# Traffic_Light_Controller.net
KiCad netlist of a schematic drawn in EAGLE
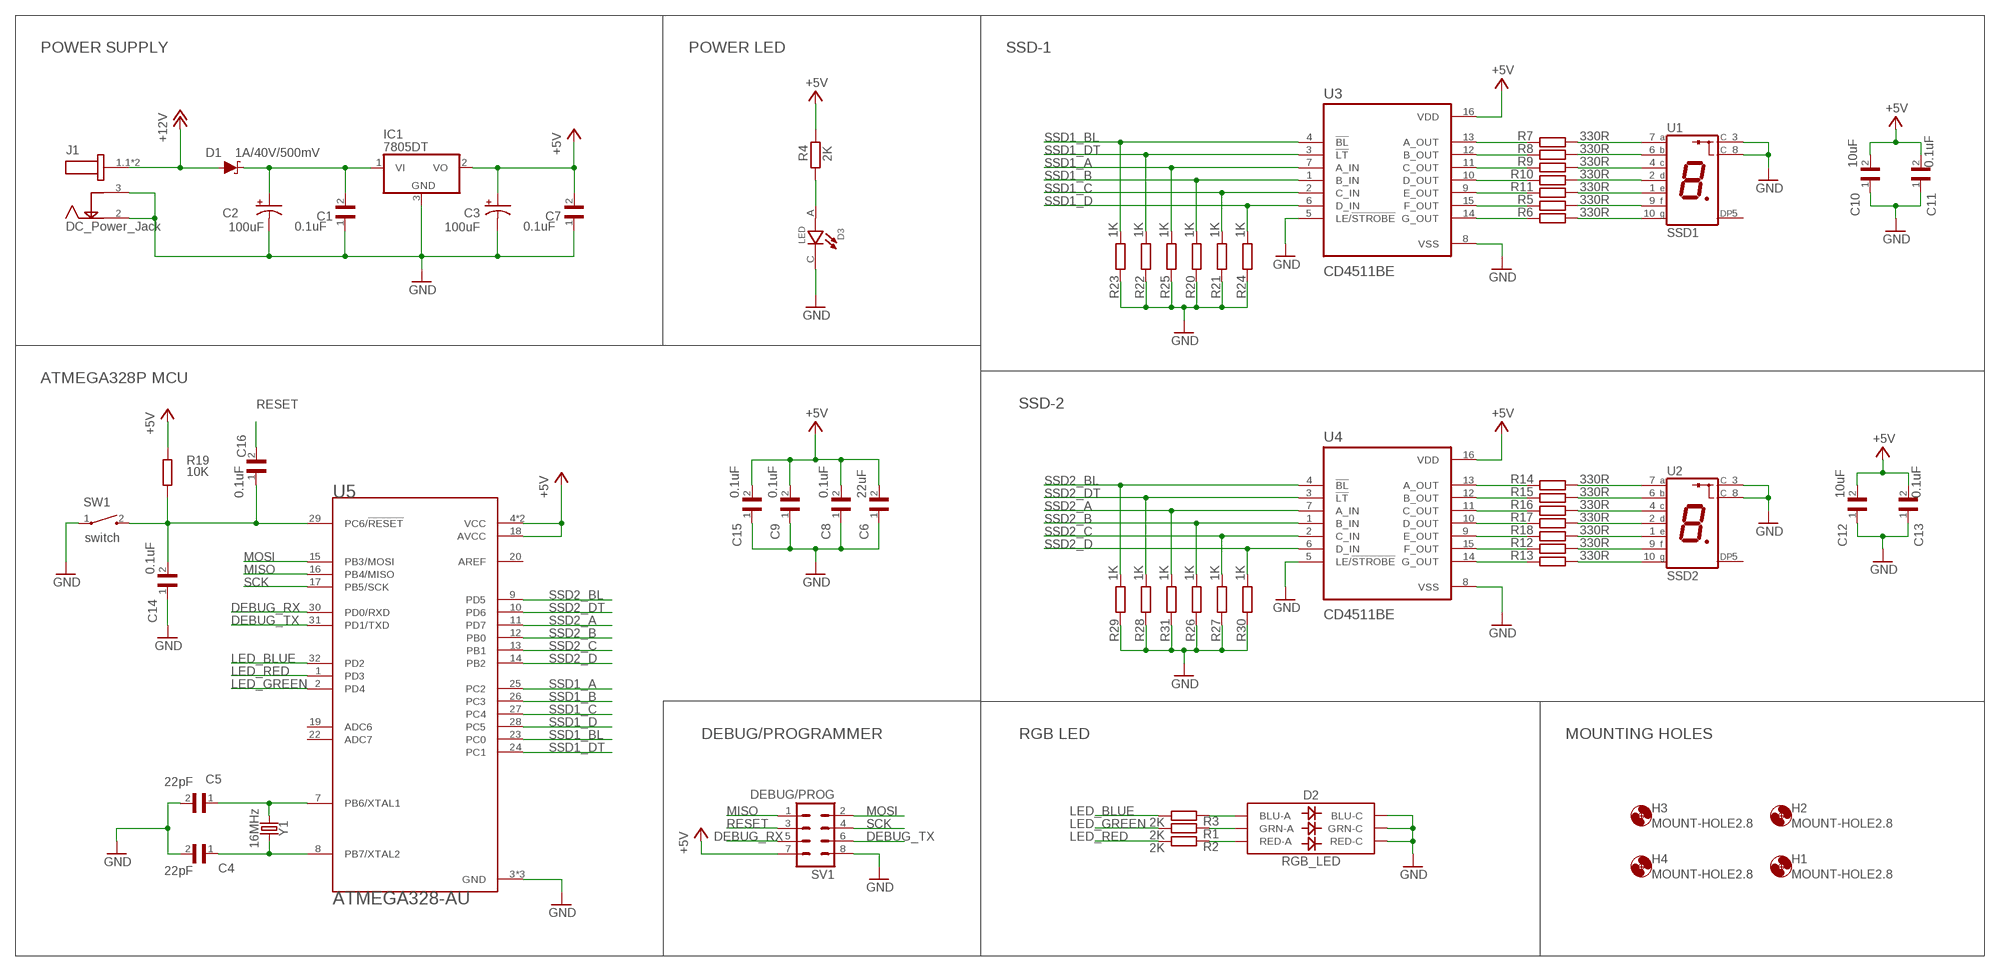
[diagram p0: schematic, sheet 1]

(export (version "E")
  (design (tool "Eeschema 10.0.6"))
  (components
    (comp (ref "C1")
      (value "0.1uF")
      (footprint "eagle-import:C0603")
      (fields (field (name "MF") "TDK") (field (name "MP") "CGA3E2X7R1H104K080AA"))
      (libsource (lib "eagle-import") (part "CAPACITOR"))
    )
    (comp (ref "C2")
      (value "100uF")
      (footprint "eagle-import:CPOL-RADIAL-2.5MM-6.5MM")
      (libsource (lib "eagle-import") (part "100UF-POLAR-RADIAL-2.5MM-25V-20%"))
    )
    (comp (ref "C3")
      (value "100uF")
      (footprint "eagle-import:CPOL-RADIAL-2.5MM-6.5MM")
      (libsource (lib "eagle-import") (part "100UF-POLAR-RADIAL-2.5MM-25V-20%"))
    )
    (comp (ref "C4")
      (value "22pF")
      (footprint "eagle-import:C0603")
      (fields (field (name "MF") "TDK") (field (name "MP") "CGA3E2X7R1H104K080AA"))
      (libsource (lib "eagle-import") (part "CAPACITOR"))
    )
    (comp (ref "C5")
      (value "22pF")
      (footprint "eagle-import:C0603")
      (fields (field (name "MF") "TDK") (field (name "MP") "CGA3E2X7R1H104K080AA"))
      (libsource (lib "eagle-import") (part "CAPACITOR"))
    )
    (comp (ref "C6")
      (value "22uF")
      (footprint "eagle-import:C0603")
      (fields (field (name "MF") "TDK") (field (name "MP") "CGA3E2X7R1H104K080AA"))
      (libsource (lib "eagle-import") (part "CAPACITOR"))
    )
    (comp (ref "C7")
      (value "0.1uF")
      (footprint "eagle-import:C0603")
      (fields (field (name "MF") "TDK") (field (name "MP") "CGA3E2X7R1H104K080AA"))
      (libsource (lib "eagle-import") (part "CAPACITOR"))
    )
    (comp (ref "C8")
      (value "0.1uF")
      (footprint "eagle-import:C0603")
      (fields (field (name "MF") "TDK") (field (name "MP") "CGA3E2X7R1H104K080AA"))
      (libsource (lib "eagle-import") (part "CAPACITOR"))
    )
    (comp (ref "C9")
      (value "0.1uF")
      (footprint "eagle-import:C0603")
      (fields (field (name "MF") "TDK") (field (name "MP") "CGA3E2X7R1H104K080AA"))
      (libsource (lib "eagle-import") (part "CAPACITOR"))
    )
    (comp (ref "C10")
      (value "10uF")
      (footprint "eagle-import:C0603")
      (fields (field (name "MF") "TDK") (field (name "MP") "CGA3E2X7R1H104K080AA"))
      (libsource (lib "eagle-import") (part "CAPACITOR"))
    )
    (comp (ref "C11")
      (value "0.1uF")
      (footprint "eagle-import:C0603")
      (fields (field (name "MF") "TDK") (field (name "MP") "CGA3E2X7R1H104K080AA"))
      (libsource (lib "eagle-import") (part "CAPACITOR"))
    )
    (comp (ref "C12")
      (value "10uF")
      (footprint "eagle-import:C0603")
      (fields (field (name "MF") "TDK") (field (name "MP") "CGA3E2X7R1H104K080AA"))
      (libsource (lib "eagle-import") (part "CAPACITOR"))
    )
    (comp (ref "C13")
      (value "0.1uF")
      (footprint "eagle-import:C0603")
      (fields (field (name "MF") "TDK") (field (name "MP") "CGA3E2X7R1H104K080AA"))
      (libsource (lib "eagle-import") (part "CAPACITOR"))
    )
    (comp (ref "C14")
      (value "0.1uF")
      (footprint "eagle-import:C0603")
      (fields (field (name "MF") "TDK") (field (name "MP") "CGA3E2X7R1H104K080AA"))
      (libsource (lib "eagle-import") (part "CAPACITOR"))
    )
    (comp (ref "C15")
      (value "0.1uF")
      (footprint "eagle-import:C0603")
      (fields (field (name "MF") "TDK") (field (name "MP") "CGA3E2X7R1H104K080AA"))
      (libsource (lib "eagle-import") (part "CAPACITOR"))
    )
    (comp (ref "C16")
      (value "0.1uF")
      (footprint "eagle-import:C0603")
      (fields (field (name "MF") "TDK") (field (name "MP") "CGA3E2X7R1H104K080AA"))
      (libsource (lib "eagle-import") (part "CAPACITOR"))
    )
    (comp (ref "D1")
      (value "1A/40V/500mV")
      (footprint "eagle-import:SMA-DIODE")
      (libsource (lib "eagle-import") (part "DIODE-SCHOTTKY-SS14"))
    )
    (comp (ref "D2")
      (value "RGB_LED")
      (footprint "eagle-import:LED-TRICOLOR-5050")
      (libsource (lib "eagle-import") (part "LED-RGBNO_IC"))
    )
    (comp (ref "D3")
      (value "LED")
      (footprint "eagle-import:LEDC1608X65N")
      (fields (field (name "MF") "Lite-On") (field (name "MP") "LTW-C191TLA"))
      (libsource (lib "eagle-import") (part "LTW-C191TLA"))
    )
    (comp (ref "H1")
      (value "MOUNT-HOLE2.8")
      (footprint "eagle-import:2,8")
      (libsource (lib "eagle-import") (part "MOUNT-HOLE2.8"))
    )
    (comp (ref "H2")
      (value "MOUNT-HOLE2.8")
      (footprint "eagle-import:2,8")
      (libsource (lib "eagle-import") (part "MOUNT-HOLE2.8"))
    )
    (comp (ref "H3")
      (value "MOUNT-HOLE2.8")
      (footprint "eagle-import:2,8")
      (libsource (lib "eagle-import") (part "MOUNT-HOLE2.8"))
    )
    (comp (ref "H4")
      (value "MOUNT-HOLE2.8")
      (footprint "eagle-import:2,8")
      (libsource (lib "eagle-import") (part "MOUNT-HOLE2.8"))
    )
    (comp (ref "IC1")
      (value "7805DT")
      (footprint "eagle-import:TO252")
      (libsource (lib "eagle-import") (part "78DT05"))
    )
    (comp (ref "J1")
      (value "DC_Power_Jack")
      (footprint "eagle-import:GCT_DCJ200-05-A-XX-X_REVA")
      (fields (field (name "MF") "Global Connector Technology") (field (name "MP") "DCJ200-05-A-K1-A"))
      (libsource (lib "eagle-import") (part "DCJ200-05-A-XX-X_REVA"))
    )
    (comp (ref "R1")
      (value "2K")
      (footprint "eagle-import:R0603")
      (fields (field (name "MF") "Yageo"))
      (libsource (lib "eagle-import") (part "RESISTOR"))
    )
    (comp (ref "R2")
      (value "2K")
      (footprint "eagle-import:R0603")
      (fields (field (name "MF") "Yageo"))
      (libsource (lib "eagle-import") (part "RESISTOR"))
    )
    (comp (ref "R3")
      (value "2K")
      (footprint "eagle-import:R0603")
      (fields (field (name "MF") "Yageo"))
      (libsource (lib "eagle-import") (part "RESISTOR"))
    )
    (comp (ref "R4")
      (value "2K")
      (footprint "eagle-import:R0603")
      (fields (field (name "MF") "Yageo"))
      (libsource (lib "eagle-import") (part "RESISTOR"))
    )
    (comp (ref "R5")
      (value "330R")
      (footprint "eagle-import:R0603")
      (fields (field (name "MF") "Yageo"))
      (libsource (lib "eagle-import") (part "RESISTOR"))
    )
    (comp (ref "R6")
      (value "330R")
      (footprint "eagle-import:R0603")
      (fields (field (name "MF") "Yageo"))
      (libsource (lib "eagle-import") (part "RESISTOR"))
    )
    (comp (ref "R7")
      (value "330R")
      (footprint "eagle-import:R0603")
      (fields (field (name "MF") "Yageo"))
      (libsource (lib "eagle-import") (part "RESISTOR"))
    )
    (comp (ref "R8")
      (value "330R")
      (footprint "eagle-import:R0603")
      (fields (field (name "MF") "Yageo"))
      (libsource (lib "eagle-import") (part "RESISTOR"))
    )
    (comp (ref "R9")
      (value "330R")
      (footprint "eagle-import:R0603")
      (fields (field (name "MF") "Yageo"))
      (libsource (lib "eagle-import") (part "RESISTOR"))
    )
    (comp (ref "R10")
      (value "330R")
      (footprint "eagle-import:R0603")
      (fields (field (name "MF") "Yageo"))
      (libsource (lib "eagle-import") (part "RESISTOR"))
    )
    (comp (ref "R11")
      (value "330R")
      (footprint "eagle-import:R0603")
      (fields (field (name "MF") "Yageo"))
      (libsource (lib "eagle-import") (part "RESISTOR"))
    )
    (comp (ref "R12")
      (value "330R")
      (footprint "eagle-import:R0603")
      (fields (field (name "MF") "Yageo"))
      (libsource (lib "eagle-import") (part "RESISTOR"))
    )
    (comp (ref "R13")
      (value "330R")
      (footprint "eagle-import:R0603")
      (fields (field (name "MF") "Yageo"))
      (libsource (lib "eagle-import") (part "RESISTOR"))
    )
    (comp (ref "R14")
      (value "330R")
      (footprint "eagle-import:R0603")
      (fields (field (name "MF") "Yageo"))
      (libsource (lib "eagle-import") (part "RESISTOR"))
    )
    (comp (ref "R15")
      (value "330R")
      (footprint "eagle-import:R0603")
      (fields (field (name "MF") "Yageo"))
      (libsource (lib "eagle-import") (part "RESISTOR"))
    )
    (comp (ref "R16")
      (value "330R")
      (footprint "eagle-import:R0603")
      (fields (field (name "MF") "Yageo"))
      (libsource (lib "eagle-import") (part "RESISTOR"))
    )
    (comp (ref "R17")
      (value "330R")
      (footprint "eagle-import:R0603")
      (fields (field (name "MF") "Yageo"))
      (libsource (lib "eagle-import") (part "RESISTOR"))
    )
    (comp (ref "R18")
      (value "330R")
      (footprint "eagle-import:R0603")
      (fields (field (name "MF") "Yageo"))
      (libsource (lib "eagle-import") (part "RESISTOR"))
    )
    (comp (ref "R19")
      (value "10K")
      (footprint "eagle-import:R0603")
      (fields (field (name "MF") "Yageo"))
      (libsource (lib "eagle-import") (part "RESISTOR"))
    )
    (comp (ref "R20")
      (value "1K")
      (footprint "eagle-import:R0603")
      (fields (field (name "MF") "Yageo"))
      (libsource (lib "eagle-import") (part "RESISTOR"))
    )
    (comp (ref "R21")
      (value "1K")
      (footprint "eagle-import:R0603")
      (fields (field (name "MF") "Yageo"))
      (libsource (lib "eagle-import") (part "RESISTOR"))
    )
    (comp (ref "R22")
      (value "1K")
      (footprint "eagle-import:R0603")
      (fields (field (name "MF") "Yageo"))
      (libsource (lib "eagle-import") (part "RESISTOR"))
    )
    (comp (ref "R23")
      (value "1K")
      (footprint "eagle-import:R0603")
      (fields (field (name "MF") "Yageo"))
      (libsource (lib "eagle-import") (part "RESISTOR"))
    )
    (comp (ref "R24")
      (value "1K")
      (footprint "eagle-import:R0603")
      (fields (field (name "MF") "Yageo"))
      (libsource (lib "eagle-import") (part "RESISTOR"))
    )
    (comp (ref "R25")
      (value "1K")
      (footprint "eagle-import:R0603")
      (fields (field (name "MF") "Yageo"))
      (libsource (lib "eagle-import") (part "RESISTOR"))
    )
    (comp (ref "R26")
      (value "1K")
      (footprint "eagle-import:R0603")
      (fields (field (name "MF") "Yageo"))
      (libsource (lib "eagle-import") (part "RESISTOR"))
    )
    (comp (ref "R27")
      (value "1K")
      (footprint "eagle-import:R0603")
      (fields (field (name "MF") "Yageo"))
      (libsource (lib "eagle-import") (part "RESISTOR"))
    )
    (comp (ref "R28")
      (value "1K")
      (footprint "eagle-import:R0603")
      (fields (field (name "MF") "Yageo"))
      (libsource (lib "eagle-import") (part "RESISTOR"))
    )
    (comp (ref "R29")
      (value "1K")
      (footprint "eagle-import:R0603")
      (fields (field (name "MF") "Yageo"))
      (libsource (lib "eagle-import") (part "RESISTOR"))
    )
    (comp (ref "R30")
      (value "1K")
      (footprint "eagle-import:R0603")
      (fields (field (name "MF") "Yageo"))
      (libsource (lib "eagle-import") (part "RESISTOR"))
    )
    (comp (ref "R31")
      (value "1K")
      (footprint "eagle-import:R0603")
      (fields (field (name "MF") "Yageo"))
      (libsource (lib "eagle-import") (part "RESISTOR"))
    )
    (comp (ref "SV1")
      (value "DEBUG/PROG")
      (footprint "eagle-import:MA04-2")
      (libsource (lib "eagle-import") (part "MA04-2"))
    )
    (comp (ref "SW1")
      (value "switch")
      (footprint "eagle-import:SW_1437566-3")
      (fields (field (name "COMMENT") "1437566-3") (field (name "MF") "TE Connectivity"))
      (libsource (lib "eagle-import") (part "1437566-3"))
    )
    (comp (ref "U1")
      (value "SSD1")
      (footprint "eagle-import:LED_SC52-11HWA")
      (fields (field (name "MF") "Kingbright") (field (name "MP") "SC52-11HWA"))
      (libsource (lib "eagle-import") (part "SC52-11HWA"))
    )
    (comp (ref "U2")
      (value "SSD2")
      (footprint "eagle-import:LED_SC52-11HWA")
      (fields (field (name "MF") "Kingbright") (field (name "MP") "SC52-11HWA"))
      (libsource (lib "eagle-import") (part "SC52-11HWA"))
    )
    (comp (ref "U3")
      (value "CD4511BE")
      (footprint "eagle-import:DIP794W45P254L1969H508Q16")
      (fields (field (name "MF") "Texas Instruments"))
      (libsource (lib "eagle-import") (part "CD4511BE"))
    )
    (comp (ref "U4")
      (value "CD4511BE")
      (footprint "eagle-import:DIP794W45P254L1969H508Q16")
      (fields (field (name "MF") "Texas Instruments"))
      (libsource (lib "eagle-import") (part "CD4511BE"))
    )
    (comp (ref "U5")
      (value "ATMEGA328-AU")
      (footprint "eagle-import:QFP80P900X900X120-32N")
      (fields (field (name "MF") "Microchip"))
      (libsource (lib "eagle-import") (part "ATMEGA328-AU"))
    )
    (comp (ref "Y1")
      (value "16MHz")
      (footprint "eagle-import:HC49US")
      (libsource (lib "eagle-import") (part "CRYSTAL-16MHZPTH-HC49US"))
    )
  )
  (nets
    (net (code "1") (name "+5V") (class "Default")
      (node (ref "C10") (pin "2") (pinfunction "2_2") (pintype "passive"))
      (node (ref "C11") (pin "2") (pinfunction "2_2") (pintype "passive"))
      (node (ref "C12") (pin "2") (pinfunction "2_2") (pintype "passive"))
      (node (ref "C13") (pin "2") (pinfunction "2_2") (pintype "passive"))
      (node (ref "C15") (pin "2") (pinfunction "2_2") (pintype "passive"))
      (node (ref "C3") (pin "1") (pinfunction "+_1") (pintype "passive"))
      (node (ref "C6") (pin "2") (pinfunction "2_2") (pintype "passive"))
      (node (ref "C7") (pin "2") (pinfunction "2_2") (pintype "passive"))
      (node (ref "C8") (pin "2") (pinfunction "2_2") (pintype "passive"))
      (node (ref "C9") (pin "2") (pinfunction "2_2") (pintype "passive"))
      (node (ref "IC1") (pin "2") (pinfunction "VO_2") (pintype "passive"))
      (node (ref "R19") (pin "2") (pinfunction "2_2") (pintype "passive"))
      (node (ref "R4") (pin "2") (pinfunction "2_2") (pintype "passive"))
      (node (ref "SV1") (pin "7") (pinfunction "7_7") (pintype "passive"))
      (node (ref "U3") (pin "16") (pinfunction "VDD_16") (pintype "power_in"))
      (node (ref "U4") (pin "16") (pinfunction "VDD_16") (pintype "power_in"))
      (node (ref "U5") (pin "18") (pinfunction "AVCC_18") (pintype "power_in"))
      (node (ref "U5") (pin "4") (pinfunction "VCC_4") (pintype "power_in"))
      (node (ref "U5") (pin "6") (pinfunction "VCC_6") (pintype "power_in"))
    )
    (net (code "2") (name "+12V") (class "Default")
      (node (ref "D1") (pin "A") (pinfunction "A_A") (pintype "passive"))
      (node (ref "J1") (pin "1.1") (pinfunction "1_1.1") (pintype "passive"))
      (node (ref "J1") (pin "1.2") (pinfunction "1_1.2") (pintype "passive"))
    )
    (net (code "3") (name "/DEBUG_RX") (class "Default")
      (node (ref "SV1") (pin "5") (pinfunction "5_5") (pintype "passive"))
      (node (ref "U5") (pin "30") (pinfunction "PD0/RXD_30") (pintype "bidirectional"))
    )
    (net (code "4") (name "/DEBUG_TX") (class "Default")
      (node (ref "SV1") (pin "6") (pinfunction "6_6") (pintype "passive"))
      (node (ref "U5") (pin "31") (pinfunction "PD1/TXD_31") (pintype "bidirectional"))
    )
    (net (code "5") (name "/LED_BLUE") (class "Default")
      (node (ref "R3") (pin "1") (pinfunction "1_1") (pintype "passive"))
      (node (ref "U5") (pin "32") (pinfunction "PD2_32") (pintype "bidirectional"))
    )
    (net (code "6") (name "/LED_GREEN") (class "Default")
      (node (ref "R1") (pin "1") (pinfunction "1_1") (pintype "passive"))
      (node (ref "U5") (pin "2") (pinfunction "PD4_2") (pintype "bidirectional"))
    )
    (net (code "7") (name "/LED_RED") (class "Default")
      (node (ref "R2") (pin "1") (pinfunction "1_1") (pintype "passive"))
      (node (ref "U5") (pin "1") (pinfunction "PD3_1") (pintype "bidirectional"))
    )
    (net (code "8") (name "/MISO") (class "Default")
      (node (ref "SV1") (pin "1") (pinfunction "1_1") (pintype "passive"))
      (node (ref "U5") (pin "16") (pinfunction "PB4/MISO_16") (pintype "bidirectional"))
    )
    (net (code "9") (name "/MOSI") (class "Default")
      (node (ref "SV1") (pin "2") (pinfunction "2_2") (pintype "passive"))
      (node (ref "U5") (pin "15") (pinfunction "PB3/MOSI_15") (pintype "bidirectional"))
    )
    (net (code "10") (name "/RESET") (class "Default")
      (node (ref "C16") (pin "2") (pinfunction "2_2") (pintype "passive"))
      (node (ref "SV1") (pin "3") (pinfunction "3_3") (pintype "passive"))
    )
    (net (code "11") (name "/SCK") (class "Default")
      (node (ref "SV1") (pin "4") (pinfunction "4_4") (pintype "passive"))
      (node (ref "U5") (pin "17") (pinfunction "PB5/SCK_17") (pintype "bidirectional"))
    )
    (net (code "12") (name "/SSD1_A") (class "Default")
      (node (ref "R25") (pin "1") (pinfunction "1_1") (pintype "passive"))
      (node (ref "U3") (pin "7") (pinfunction "A_IN_7") (pintype "input"))
      (node (ref "U5") (pin "25") (pinfunction "PC2_25") (pintype "bidirectional"))
    )
    (net (code "13") (name "/SSD1_B") (class "Default")
      (node (ref "R20") (pin "1") (pinfunction "1_1") (pintype "passive"))
      (node (ref "U3") (pin "1") (pinfunction "B_IN_1") (pintype "input"))
      (node (ref "U5") (pin "26") (pinfunction "PC3_26") (pintype "bidirectional"))
    )
    (net (code "14") (name "/SSD1_BL") (class "Default")
      (node (ref "R23") (pin "1") (pinfunction "1_1") (pintype "passive"))
      (node (ref "U3") (pin "4") (pinfunction "~{BL}_4") (pintype "input"))
      (node (ref "U5") (pin "23") (pinfunction "PC0_23") (pintype "bidirectional"))
    )
    (net (code "15") (name "/SSD1_C") (class "Default")
      (node (ref "R21") (pin "1") (pinfunction "1_1") (pintype "passive"))
      (node (ref "U3") (pin "2") (pinfunction "C_IN_2") (pintype "input"))
      (node (ref "U5") (pin "27") (pinfunction "PC4_27") (pintype "bidirectional"))
    )
    (net (code "16") (name "/SSD1_D") (class "Default")
      (node (ref "R24") (pin "1") (pinfunction "1_1") (pintype "passive"))
      (node (ref "U3") (pin "6") (pinfunction "D_IN_6") (pintype "input"))
      (node (ref "U5") (pin "28") (pinfunction "PC5_28") (pintype "bidirectional"))
    )
    (net (code "17") (name "/SSD1_DT") (class "Default")
      (node (ref "R22") (pin "1") (pinfunction "1_1") (pintype "passive"))
      (node (ref "U3") (pin "3") (pinfunction "~{LT}_3") (pintype "input"))
      (node (ref "U5") (pin "24") (pinfunction "PC1_24") (pintype "bidirectional"))
    )
    (net (code "18") (name "/SSD2_A") (class "Default")
      (node (ref "R31") (pin "1") (pinfunction "1_1") (pintype "passive"))
      (node (ref "U4") (pin "7") (pinfunction "A_IN_7") (pintype "input"))
      (node (ref "U5") (pin "11") (pinfunction "PD7_11") (pintype "bidirectional"))
    )
    (net (code "19") (name "/SSD2_B") (class "Default")
      (node (ref "R26") (pin "1") (pinfunction "1_1") (pintype "passive"))
      (node (ref "U4") (pin "1") (pinfunction "B_IN_1") (pintype "input"))
      (node (ref "U5") (pin "12") (pinfunction "PB0_12") (pintype "bidirectional"))
    )
    (net (code "20") (name "/SSD2_BL") (class "Default")
      (node (ref "R29") (pin "1") (pinfunction "1_1") (pintype "passive"))
      (node (ref "U4") (pin "4") (pinfunction "~{BL}_4") (pintype "input"))
      (node (ref "U5") (pin "9") (pinfunction "PD5_9") (pintype "bidirectional"))
    )
    (net (code "21") (name "/SSD2_C") (class "Default")
      (node (ref "R27") (pin "1") (pinfunction "1_1") (pintype "passive"))
      (node (ref "U4") (pin "2") (pinfunction "C_IN_2") (pintype "input"))
      (node (ref "U5") (pin "13") (pinfunction "PB1_13") (pintype "bidirectional"))
    )
    (net (code "22") (name "/SSD2_D") (class "Default")
      (node (ref "R30") (pin "1") (pinfunction "1_1") (pintype "passive"))
      (node (ref "U4") (pin "6") (pinfunction "D_IN_6") (pintype "input"))
      (node (ref "U5") (pin "14") (pinfunction "PB2_14") (pintype "bidirectional"))
    )
    (net (code "23") (name "/SSD2_DT") (class "Default")
      (node (ref "R28") (pin "1") (pinfunction "1_1") (pintype "passive"))
      (node (ref "U4") (pin "3") (pinfunction "~{LT}_3") (pintype "input"))
      (node (ref "U5") (pin "10") (pinfunction "PD6_10") (pintype "bidirectional"))
    )
    (net (code "24") (name "GND") (class "Default")
      (node (ref "C1") (pin "1") (pinfunction "1_1") (pintype "passive"))
      (node (ref "C10") (pin "1") (pinfunction "1_1") (pintype "passive"))
      (node (ref "C11") (pin "1") (pinfunction "1_1") (pintype "passive"))
      (node (ref "C12") (pin "1") (pinfunction "1_1") (pintype "passive"))
      (node (ref "C13") (pin "1") (pinfunction "1_1") (pintype "passive"))
      (node (ref "C14") (pin "1") (pinfunction "1_1") (pintype "passive"))
      (node (ref "C15") (pin "1") (pinfunction "1_1") (pintype "passive"))
      (node (ref "C2") (pin "2") (pinfunction "-_2") (pintype "passive"))
      (node (ref "C3") (pin "2") (pinfunction "-_2") (pintype "passive"))
      (node (ref "C4") (pin "2") (pinfunction "2_2") (pintype "passive"))
      (node (ref "C5") (pin "2") (pinfunction "2_2") (pintype "passive"))
      (node (ref "C6") (pin "1") (pinfunction "1_1") (pintype "passive"))
      (node (ref "C7") (pin "1") (pinfunction "1_1") (pintype "passive"))
      (node (ref "C8") (pin "1") (pinfunction "1_1") (pintype "passive"))
      (node (ref "C9") (pin "1") (pinfunction "1_1") (pintype "passive"))
      (node (ref "D2") (pin "4") (pinfunction "BLU-C_4") (pintype "bidirectional"))
      (node (ref "D2") (pin "5") (pinfunction "RED-C_5") (pintype "bidirectional"))
      (node (ref "D2") (pin "6") (pinfunction "GRN-C_6") (pintype "bidirectional"))
      (node (ref "D3") (pin "C") (pinfunction "C_C") (pintype "passive"))
      (node (ref "IC1") (pin "3") (pinfunction "GND_3") (pintype "passive"))
      (node (ref "J1") (pin "2") (pinfunction "2_2") (pintype "passive"))
      (node (ref "J1") (pin "3") (pinfunction "3_3") (pintype "passive"))
      (node (ref "R20") (pin "2") (pinfunction "2_2") (pintype "passive"))
      (node (ref "R21") (pin "2") (pinfunction "2_2") (pintype "passive"))
      (node (ref "R22") (pin "2") (pinfunction "2_2") (pintype "passive"))
      (node (ref "R23") (pin "2") (pinfunction "2_2") (pintype "passive"))
      (node (ref "R24") (pin "2") (pinfunction "2_2") (pintype "passive"))
      (node (ref "R25") (pin "2") (pinfunction "2_2") (pintype "passive"))
      (node (ref "R26") (pin "2") (pinfunction "2_2") (pintype "passive"))
      (node (ref "R27") (pin "2") (pinfunction "2_2") (pintype "passive"))
      (node (ref "R28") (pin "2") (pinfunction "2_2") (pintype "passive"))
      (node (ref "R29") (pin "2") (pinfunction "2_2") (pintype "passive"))
      (node (ref "R30") (pin "2") (pinfunction "2_2") (pintype "passive"))
      (node (ref "R31") (pin "2") (pinfunction "2_2") (pintype "passive"))
      (node (ref "SV1") (pin "8") (pinfunction "8_8") (pintype "passive"))
      (node (ref "SW1") (pin "1") (pinfunction "1_1") (pintype "passive"))
      (node (ref "U1") (pin "3") (pinfunction "C_3") (pintype "passive"))
      (node (ref "U1") (pin "8") (pinfunction "C_8") (pintype "passive"))
      (node (ref "U2") (pin "3") (pinfunction "C_3") (pintype "passive"))
      (node (ref "U2") (pin "8") (pinfunction "C_8") (pintype "passive"))
      (node (ref "U3") (pin "5") (pinfunction "LE/~{STROBE}_5") (pintype "input"))
      (node (ref "U3") (pin "8") (pinfunction "VSS_8") (pintype "power_in"))
      (node (ref "U4") (pin "5") (pinfunction "LE/~{STROBE}_5") (pintype "input"))
      (node (ref "U4") (pin "8") (pinfunction "VSS_8") (pintype "power_in"))
      (node (ref "U5") (pin "21") (pinfunction "GND_21") (pintype "power_in"))
      (node (ref "U5") (pin "3") (pinfunction "GND_3") (pintype "power_in"))
      (node (ref "U5") (pin "5") (pinfunction "GND_5") (pintype "power_in"))
    )
    (net (code "25") (name "Net-(C2-+)") (class "Default")
      (node (ref "C1") (pin "2") (pinfunction "2_2") (pintype "passive"))
      (node (ref "C2") (pin "1") (pinfunction "+_1") (pintype "passive"))
      (node (ref "D1") (pin "C") (pinfunction "C_C") (pintype "passive"))
      (node (ref "IC1") (pin "1") (pinfunction "VI_1") (pintype "input"))
    )
    (net (code "26") (name "Net-(D2-BLU-A)") (class "Default")
      (node (ref "D2") (pin "3") (pinfunction "BLU-A_3") (pintype "bidirectional"))
      (node (ref "R3") (pin "2") (pinfunction "2_2") (pintype "passive"))
    )
    (net (code "27") (name "Net-(D2-GRN-A)") (class "Default")
      (node (ref "D2") (pin "1") (pinfunction "GRN-A_1") (pintype "bidirectional"))
      (node (ref "R1") (pin "2") (pinfunction "2_2") (pintype "passive"))
    )
    (net (code "28") (name "Net-(D2-RED-A)") (class "Default")
      (node (ref "D2") (pin "2") (pinfunction "RED-A_2") (pintype "bidirectional"))
      (node (ref "R2") (pin "2") (pinfunction "2_2") (pintype "passive"))
    )
    (net (code "29") (name "Net-(D3-PadA)") (class "Default")
      (node (ref "D3") (pin "A") (pinfunction "A_A") (pintype "passive"))
      (node (ref "R4") (pin "1") (pinfunction "1_1") (pintype "passive"))
    )
    (net (code "30") (name "Net-(R9-Pad1)") (class "Default")
      (node (ref "R9") (pin "1") (pinfunction "1_1") (pintype "passive"))
      (node (ref "U1") (pin "4") (pinfunction "C_4") (pintype "passive"))
    )
    (net (code "31") (name "Net-(R16-Pad1)") (class "Default")
      (node (ref "R16") (pin "1") (pinfunction "1_1") (pintype "passive"))
      (node (ref "U2") (pin "4") (pinfunction "C_4") (pintype "passive"))
    )
    (net (code "32") (name "Net-(U1-A)") (class "Default")
      (node (ref "R7") (pin "1") (pinfunction "1_1") (pintype "passive"))
      (node (ref "U1") (pin "7") (pinfunction "A_7") (pintype "passive"))
    )
    (net (code "33") (name "Net-(U1-B)") (class "Default")
      (node (ref "R8") (pin "1") (pinfunction "1_1") (pintype "passive"))
      (node (ref "U1") (pin "6") (pinfunction "B_6") (pintype "passive"))
    )
    (net (code "34") (name "Net-(U1-D)") (class "Default")
      (node (ref "R10") (pin "1") (pinfunction "1_1") (pintype "passive"))
      (node (ref "U1") (pin "2") (pinfunction "D_2") (pintype "passive"))
    )
    (net (code "35") (name "Net-(U1-E)") (class "Default")
      (node (ref "R11") (pin "1") (pinfunction "1_1") (pintype "passive"))
      (node (ref "U1") (pin "1") (pinfunction "E_1") (pintype "passive"))
    )
    (net (code "36") (name "Net-(U1-F)") (class "Default")
      (node (ref "R5") (pin "1") (pinfunction "1_1") (pintype "passive"))
      (node (ref "U1") (pin "9") (pinfunction "F_9") (pintype "passive"))
    )
    (net (code "37") (name "Net-(U1-G)") (class "Default")
      (node (ref "R6") (pin "1") (pinfunction "1_1") (pintype "passive"))
      (node (ref "U1") (pin "10") (pinfunction "G_10") (pintype "passive"))
    )
    (net (code "38") (name "Net-(U2-A)") (class "Default")
      (node (ref "R14") (pin "1") (pinfunction "1_1") (pintype "passive"))
      (node (ref "U2") (pin "7") (pinfunction "A_7") (pintype "passive"))
    )
    (net (code "39") (name "Net-(U2-B)") (class "Default")
      (node (ref "R15") (pin "1") (pinfunction "1_1") (pintype "passive"))
      (node (ref "U2") (pin "6") (pinfunction "B_6") (pintype "passive"))
    )
    (net (code "40") (name "Net-(U2-D)") (class "Default")
      (node (ref "R17") (pin "1") (pinfunction "1_1") (pintype "passive"))
      (node (ref "U2") (pin "2") (pinfunction "D_2") (pintype "passive"))
    )
    (net (code "41") (name "Net-(U2-E)") (class "Default")
      (node (ref "R18") (pin "1") (pinfunction "1_1") (pintype "passive"))
      (node (ref "U2") (pin "1") (pinfunction "E_1") (pintype "passive"))
    )
    (net (code "42") (name "Net-(U2-F)") (class "Default")
      (node (ref "R12") (pin "1") (pinfunction "1_1") (pintype "passive"))
      (node (ref "U2") (pin "9") (pinfunction "F_9") (pintype "passive"))
    )
    (net (code "43") (name "Net-(U2-G)") (class "Default")
      (node (ref "R13") (pin "1") (pinfunction "1_1") (pintype "passive"))
      (node (ref "U2") (pin "10") (pinfunction "G_10") (pintype "passive"))
    )
    (net (code "44") (name "Net-(U3-A_OUT)") (class "Default")
      (node (ref "R7") (pin "2") (pinfunction "2_2") (pintype "passive"))
      (node (ref "U3") (pin "13") (pinfunction "A_OUT_13") (pintype "output"))
    )
    (net (code "45") (name "Net-(U3-B_OUT)") (class "Default")
      (node (ref "R8") (pin "2") (pinfunction "2_2") (pintype "passive"))
      (node (ref "U3") (pin "12") (pinfunction "B_OUT_12") (pintype "output"))
    )
    (net (code "46") (name "Net-(U3-C_OUT)") (class "Default")
      (node (ref "R9") (pin "2") (pinfunction "2_2") (pintype "passive"))
      (node (ref "U3") (pin "11") (pinfunction "C_OUT_11") (pintype "output"))
    )
    (net (code "47") (name "Net-(U3-D_OUT)") (class "Default")
      (node (ref "R10") (pin "2") (pinfunction "2_2") (pintype "passive"))
      (node (ref "U3") (pin "10") (pinfunction "D_OUT_10") (pintype "output"))
    )
    (net (code "48") (name "Net-(U3-E_OUT)") (class "Default")
      (node (ref "R11") (pin "2") (pinfunction "2_2") (pintype "passive"))
      (node (ref "U3") (pin "9") (pinfunction "E_OUT_9") (pintype "output"))
    )
    (net (code "49") (name "Net-(U3-F_OUT)") (class "Default")
      (node (ref "R5") (pin "2") (pinfunction "2_2") (pintype "passive"))
      (node (ref "U3") (pin "15") (pinfunction "F_OUT_15") (pintype "output"))
    )
    (net (code "50") (name "Net-(U3-G_OUT)") (class "Default")
      (node (ref "R6") (pin "2") (pinfunction "2_2") (pintype "passive"))
      (node (ref "U3") (pin "14") (pinfunction "G_OUT_14") (pintype "output"))
    )
    (net (code "51") (name "Net-(U4-A_OUT)") (class "Default")
      (node (ref "R14") (pin "2") (pinfunction "2_2") (pintype "passive"))
      (node (ref "U4") (pin "13") (pinfunction "A_OUT_13") (pintype "output"))
    )
    (net (code "52") (name "Net-(U4-B_OUT)") (class "Default")
      (node (ref "R15") (pin "2") (pinfunction "2_2") (pintype "passive"))
      (node (ref "U4") (pin "12") (pinfunction "B_OUT_12") (pintype "output"))
    )
    (net (code "53") (name "Net-(U4-C_OUT)") (class "Default")
      (node (ref "R16") (pin "2") (pinfunction "2_2") (pintype "passive"))
      (node (ref "U4") (pin "11") (pinfunction "C_OUT_11") (pintype "output"))
    )
    (net (code "54") (name "Net-(U4-D_OUT)") (class "Default")
      (node (ref "R17") (pin "2") (pinfunction "2_2") (pintype "passive"))
      (node (ref "U4") (pin "10") (pinfunction "D_OUT_10") (pintype "output"))
    )
    (net (code "55") (name "Net-(U4-E_OUT)") (class "Default")
      (node (ref "R18") (pin "2") (pinfunction "2_2") (pintype "passive"))
      (node (ref "U4") (pin "9") (pinfunction "E_OUT_9") (pintype "output"))
    )
    (net (code "56") (name "Net-(U4-F_OUT)") (class "Default")
      (node (ref "R12") (pin "2") (pinfunction "2_2") (pintype "passive"))
      (node (ref "U4") (pin "15") (pinfunction "F_OUT_15") (pintype "output"))
    )
    (net (code "57") (name "Net-(U4-G_OUT)") (class "Default")
      (node (ref "R13") (pin "2") (pinfunction "2_2") (pintype "passive"))
      (node (ref "U4") (pin "14") (pinfunction "G_OUT_14") (pintype "output"))
    )
    (net (code "58") (name "Net-(U5-PB6{slash}XTAL1)") (class "Default")
      (node (ref "C5") (pin "1") (pinfunction "1_1") (pintype "passive"))
      (node (ref "U5") (pin "7") (pinfunction "PB6/XTAL1_7") (pintype "bidirectional"))
      (node (ref "Y1") (pin "1") (pinfunction "1_1") (pintype "passive"))
    )
    (net (code "59") (name "Net-(U5-PB7{slash}XTAL2)") (class "Default")
      (node (ref "C4") (pin "1") (pinfunction "1_1") (pintype "passive"))
      (node (ref "U5") (pin "8") (pinfunction "PB7/XTAL2_8") (pintype "bidirectional"))
      (node (ref "Y1") (pin "2") (pinfunction "2_2") (pintype "passive"))
    )
    (net (code "60") (name "Net-(U5-PC6{slash}~{RESET})") (class "Default")
      (node (ref "C14") (pin "2") (pinfunction "2_2") (pintype "passive"))
      (node (ref "C16") (pin "1") (pinfunction "1_1") (pintype "passive"))
      (node (ref "R19") (pin "1") (pinfunction "1_1") (pintype "passive"))
      (node (ref "SW1") (pin "2") (pinfunction "2_2") (pintype "passive"))
      (node (ref "U5") (pin "29") (pinfunction "PC6/~{RESET}_29") (pintype "bidirectional"))
    )
    (net (code "61") (name "unconnected-(U1-DP-Pad5)") (class "Default")
      (node (ref "U1") (pin "5") (pinfunction "DP_5") (pintype "passive"))
    )
    (net (code "62") (name "unconnected-(U2-DP-Pad5)") (class "Default")
      (node (ref "U2") (pin "5") (pinfunction "DP_5") (pintype "passive"))
    )
    (net (code "63") (name "unconnected-(U5-ADC6-Pad19)") (class "Default")
      (node (ref "U5") (pin "19") (pinfunction "ADC6_19") (pintype "bidirectional"))
    )
    (net (code "64") (name "unconnected-(U5-ADC7-Pad22)") (class "Default")
      (node (ref "U5") (pin "22") (pinfunction "ADC7_22") (pintype "bidirectional"))
    )
    (net (code "65") (name "unconnected-(U5-AREF-Pad20)") (class "Default")
      (node (ref "U5") (pin "20") (pinfunction "AREF_20") (pintype "input"))
    )
  )
)
